# blinkyboard.net
KiCad netlist of a schematic drawn in EAGLE
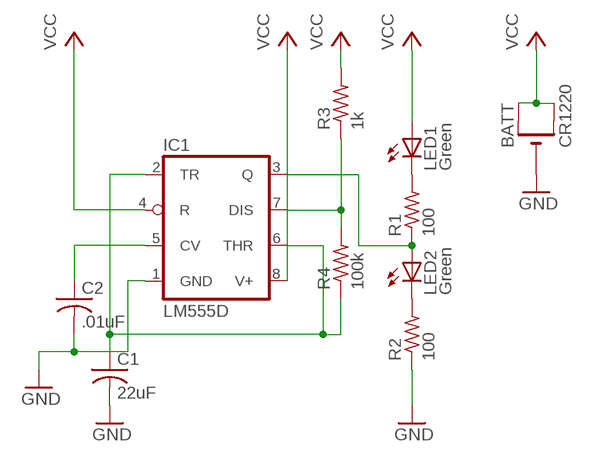
[diagram p0: schematic, sheet 1]

(export (version "E")
  (design (tool "Eeschema 10.0.6"))
  (components
    (comp (ref "BATT")
      (value "CR1220")
      (footprint "eagle-import:CR1220-SMD")
      (fields (field (name "MF") "KEYSTONE") (field (name "MPN") "3080"))
      (libsource (lib "eagle-import") (part "CR1220SMT"))
    )
    (comp (ref "C1")
      (value "22uF")
      (footprint "eagle-import:C0805")
      (fields (field (name "MF") "AVX") (field (name "MPN") "06035C224KAT2A"))
      (libsource (lib "eagle-import") (part "C-USC0805"))
    )
    (comp (ref "C2")
      (value ".01uF")
      (footprint "eagle-import:C0805")
      (fields (field (name "MF") "NTE ELECTRONICS") (field (name "MPN") "CML103J100"))
      (libsource (lib "eagle-import") (part "C-USC0805"))
    )
    (comp (ref "IC1")
      (value "LM555D")
      (footprint "eagle-import:SO08")
      (fields (field (name "MF") "TEXAS INSTRUMENTS") (field (name "MPN") "TLC555CDR"))
      (libsource (lib "eagle-import") (part "555DLM"))
    )
    (comp (ref "LED1")
      (value "Green")
      (footprint "eagle-import:CHIPLED_0805")
      (fields (field (name "MF") "LUMEX") (field (name "MPN") "SML-LX0805SUGC-TR"))
      (libsource (lib "eagle-import") (part "LEDCHIPLED_0805"))
    )
    (comp (ref "LED2")
      (value "Green")
      (footprint "eagle-import:CHIPLED_0805")
      (fields (field (name "MF") "LUMEX") (field (name "MPN") "SML-LX0805SUGC-TR"))
      (libsource (lib "eagle-import") (part "LEDCHIPLED_0805"))
    )
    (comp (ref "R1")
      (value "100")
      (footprint "eagle-import:R0805")
      (fields (field (name "MF") "VISHAY") (field (name "MPN") "CRCW0805100RJNEA"))
      (libsource (lib "eagle-import") (part "R-US_R0805"))
    )
    (comp (ref "R2")
      (value "100")
      (footprint "eagle-import:R0805")
      (fields (field (name "MF") "VISHAY") (field (name "MPN") "CRCW0805100RJNEA"))
      (libsource (lib "eagle-import") (part "R-US_R0805"))
    )
    (comp (ref "R3")
      (value "1k")
      (footprint "eagle-import:R0805")
      (fields (field (name "MF") "VISHAY") (field (name "MPN") "CRCW08051K00FKEB"))
      (libsource (lib "eagle-import") (part "R-US_R0805"))
    )
    (comp (ref "R4")
      (value "100k")
      (footprint "eagle-import:R0805")
      (fields (field (name "MF") "MULTICOMP PRO") (field (name "MPN") "MCHP05W4F1003T5E"))
      (libsource (lib "eagle-import") (part "R-US_R0805"))
    )
  )
  (nets
    (net (code "1") (name "GND") (class "Default")
      (node (ref "BATT") (pin "-") (pinfunction "-_-") (pintype "passive"))
      (node (ref "C1") (pin "2") (pinfunction "2_2") (pintype "passive"))
      (node (ref "C2") (pin "2") (pinfunction "2_2") (pintype "passive"))
      (node (ref "IC1") (pin "1") (pinfunction "GND_1") (pintype "power_in"))
      (node (ref "R2") (pin "1") (pinfunction "1_1") (pintype "passive"))
    )
    (net (code "2") (name "Net-(IC1-CV)") (class "Default")
      (node (ref "C2") (pin "1") (pinfunction "1_1") (pintype "passive"))
      (node (ref "IC1") (pin "5") (pinfunction "CV_5") (pintype "input"))
    )
    (net (code "3") (name "Net-(IC1-DIS)") (class "Default")
      (node (ref "IC1") (pin "7") (pinfunction "DIS_7") (pintype "input"))
      (node (ref "R3") (pin "1") (pinfunction "1_1") (pintype "passive"))
      (node (ref "R4") (pin "2") (pinfunction "2_2") (pintype "passive"))
    )
    (net (code "4") (name "Net-(IC1-Q)") (class "Default")
      (node (ref "IC1") (pin "3") (pinfunction "Q_3") (pintype "output"))
      (node (ref "LED2") (pin "A") (pinfunction "A_A") (pintype "passive"))
      (node (ref "R1") (pin "1") (pinfunction "1_1") (pintype "passive"))
    )
    (net (code "5") (name "Net-(IC1-THR)") (class "Default")
      (node (ref "C1") (pin "1") (pinfunction "1_1") (pintype "passive"))
      (node (ref "IC1") (pin "2") (pinfunction "TR_2") (pintype "input"))
      (node (ref "IC1") (pin "6") (pinfunction "THR_6") (pintype "input"))
      (node (ref "R4") (pin "1") (pinfunction "1_1") (pintype "passive"))
    )
    (net (code "6") (name "Net-(LED1-PadC)") (class "Default")
      (node (ref "LED1") (pin "C") (pinfunction "C_C") (pintype "passive"))
      (node (ref "R1") (pin "2") (pinfunction "2_2") (pintype "passive"))
    )
    (net (code "7") (name "Net-(LED2-PadC)") (class "Default")
      (node (ref "LED2") (pin "C") (pinfunction "C_C") (pintype "passive"))
      (node (ref "R2") (pin "2") (pinfunction "2_2") (pintype "passive"))
    )
    (net (code "8") (name "VCC") (class "Default")
      (node (ref "BATT") (pin "+$1") (pinfunction "+_+$1") (pintype "passive"))
      (node (ref "BATT") (pin "+$2") (pinfunction "+1_+$2") (pintype "passive"))
      (node (ref "IC1") (pin "4") (pinfunction "R_4") (pintype "input"))
      (node (ref "IC1") (pin "8") (pinfunction "V+_8") (pintype "power_in"))
      (node (ref "LED1") (pin "A") (pinfunction "A_A") (pintype "passive"))
      (node (ref "R3") (pin "2") (pinfunction "2_2") (pintype "passive"))
    )
  )
)
